# Adapter-CMRI8-RJ45.net
KiCad netlist of a schematic drawn in EAGLE
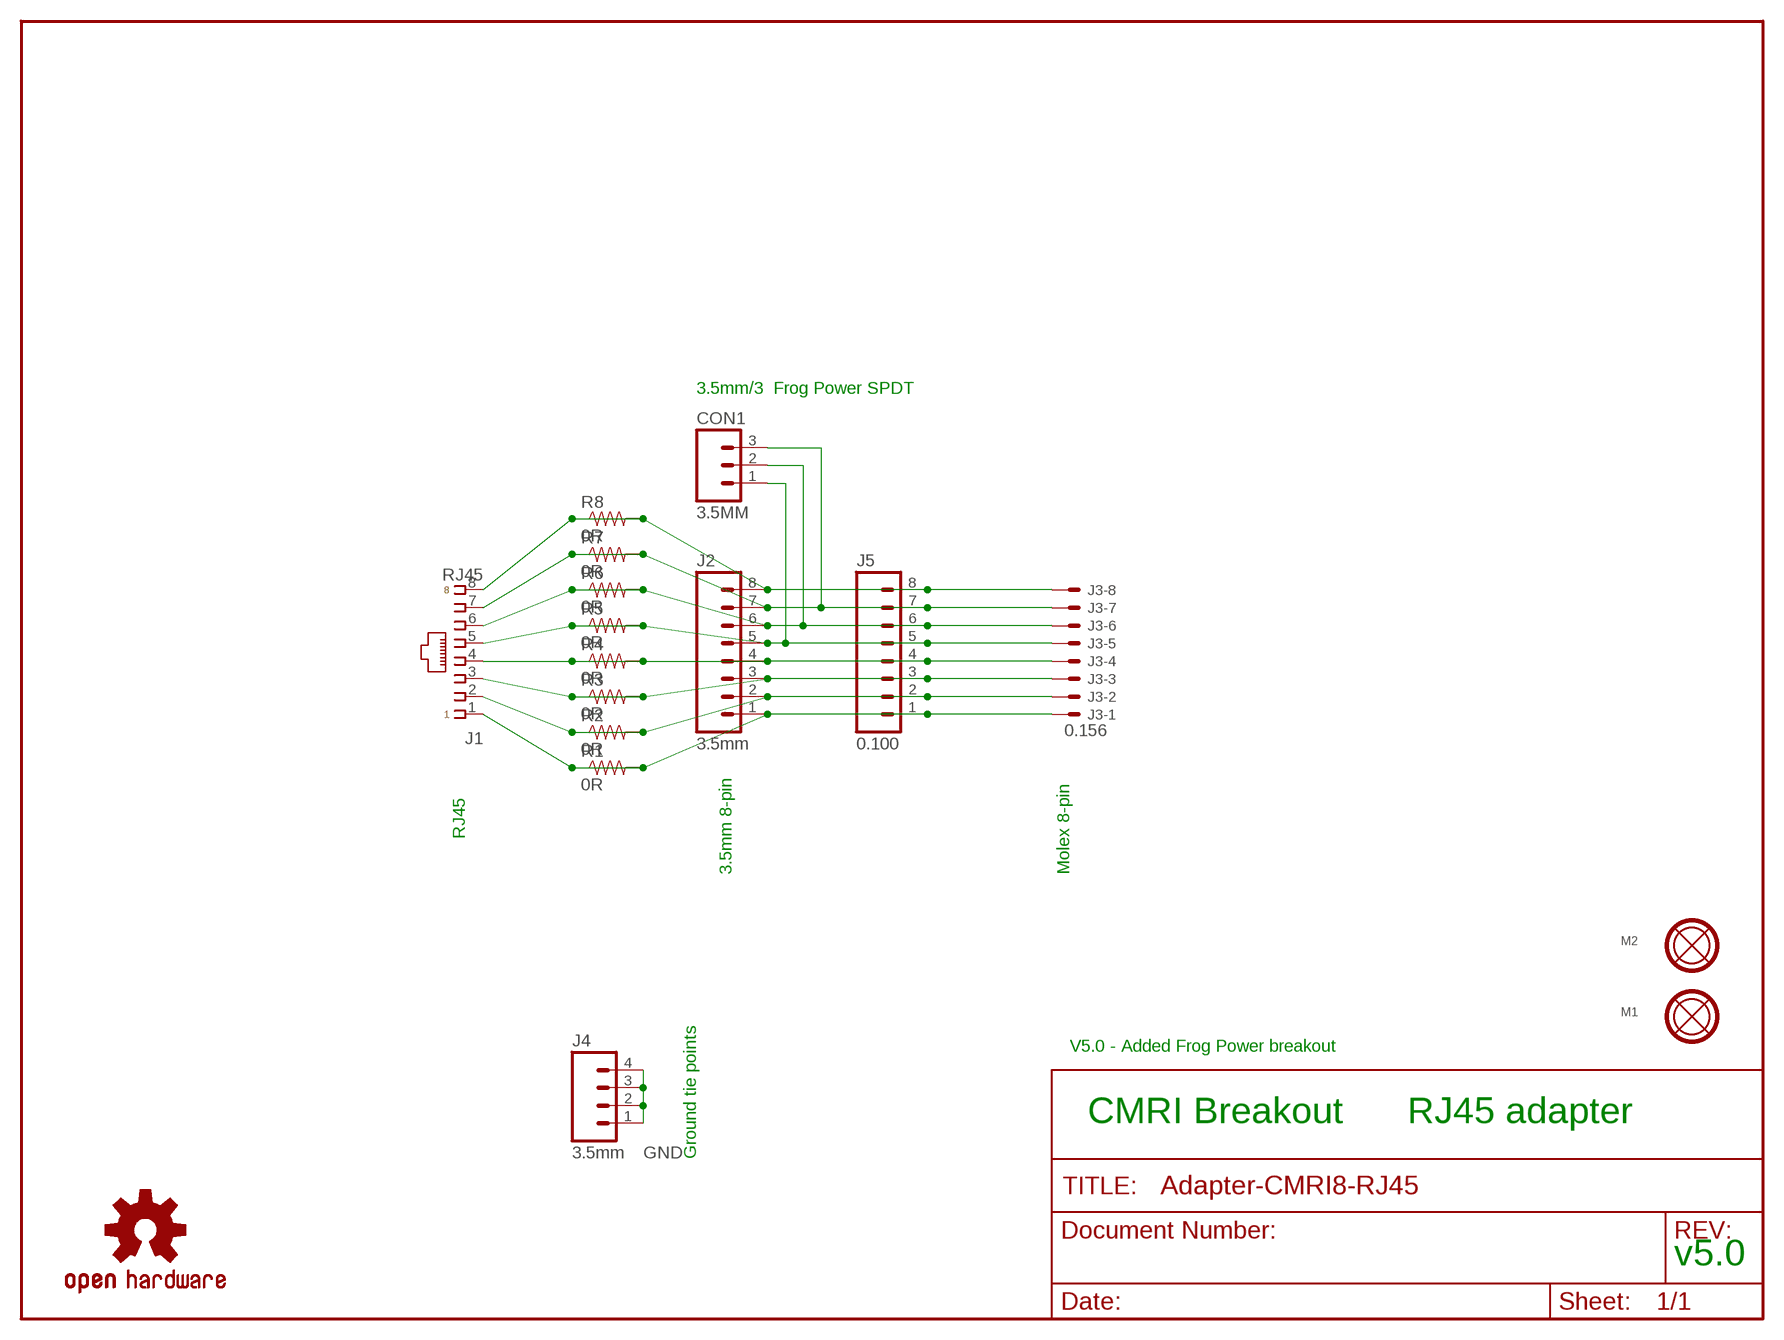
[diagram p0: schematic, sheet 1]

(export (version "E")
  (design (tool "Eeschema 10.0.6"))
  (components
    (comp (ref "CON1")
      (value "3.5MM")
      (footprint "eagle-import:SCREWTERMINAL-3.5MM-3_LOCK.007S")
      (libsource (lib "eagle-import") (part "CONNECTOR-M033.5MM-LOCK"))
    )
    (comp (ref "J1")
      (value "RJ45")
      (footprint "eagle-import:RJ45-NO-SHIELD")
      (libsource (lib "eagle-import") (part "CONNECTOR-RJ45-FRONT"))
    )
    (comp (ref "J2")
      (value "3.5mm")
      (footprint "eagle-import:SCREWTERMINAL-3.5MM-8")
      (libsource (lib "eagle-import") (part "CONNECTOR-M083.5MM-8"))
    )
    (comp (ref "J3")
      (value "0.156")
      (footprint "eagle-import:KK-156-8-F")
      (libsource (lib "eagle-import") (part "KK-156-8F"))
    )
    (comp (ref "J4")
      (value "3.5mm")
      (footprint "eagle-import:SCREWTERMINAL-3.5MM-4_LOCK")
      (libsource (lib "eagle-import") (part "CONNECTOR-M04SCREW_LOCK"))
    )
    (comp (ref "J5")
      (value "0.100")
      (footprint "eagle-import:1X08_LOCK")
      (libsource (lib "eagle-import") (part "CONNECTOR-M08LOCK"))
    )
    (comp (ref "M1")
      (value "MOUNTINGHOLE")
      (footprint "eagle-import:MOUNTINGHOLE")
      (libsource (lib "eagle-import") (part "MOUNTINGHOLE"))
    )
    (comp (ref "M2")
      (value "MOUNTINGHOLE")
      (footprint "eagle-import:MOUNTINGHOLE")
      (libsource (lib "eagle-import") (part "MOUNTINGHOLE"))
    )
    (comp (ref "R1")
      (value "0R")
      (footprint "eagle-import:AXIAL-0.4-RES")
      (libsource (lib "eagle-import") (part "RPTH04"))
    )
    (comp (ref "R2")
      (value "0R")
      (footprint "eagle-import:AXIAL-0.4-RES")
      (libsource (lib "eagle-import") (part "RPTH04"))
    )
    (comp (ref "R3")
      (value "0R")
      (footprint "eagle-import:AXIAL-0.4-RES")
      (libsource (lib "eagle-import") (part "RPTH04"))
    )
    (comp (ref "R4")
      (value "0R")
      (footprint "eagle-import:AXIAL-0.4-RES")
      (libsource (lib "eagle-import") (part "RPTH04"))
    )
    (comp (ref "R5")
      (value "0R")
      (footprint "eagle-import:AXIAL-0.4-RES")
      (libsource (lib "eagle-import") (part "RPTH04"))
    )
    (comp (ref "R6")
      (value "0R")
      (footprint "eagle-import:AXIAL-0.4-RES")
      (libsource (lib "eagle-import") (part "RPTH04"))
    )
    (comp (ref "R7")
      (value "0R")
      (footprint "eagle-import:AXIAL-0.4-RES")
      (libsource (lib "eagle-import") (part "RPTH04"))
    )
    (comp (ref "R8")
      (value "0R")
      (footprint "eagle-import:AXIAL-0.4-RES")
      (libsource (lib "eagle-import") (part "RPTH04"))
    )
    (comp (ref "U$1")
      (value "OSHW")
      (footprint "eagle-import:OSHW-LOGO-L")
      (libsource (lib "eagle-import") (part "DOC-OSHW-LOGO-L"))
    )
  )
  (nets
    (net (code "1") (name "/GND") (class "Default")
      (node (ref "J4") (pin "1") (pinfunction "1_1") (pintype "passive"))
      (node (ref "J4") (pin "2") (pinfunction "2_2") (pintype "passive"))
      (node (ref "J4") (pin "3") (pinfunction "3_3") (pintype "passive"))
      (node (ref "J4") (pin "4") (pinfunction "4_4") (pintype "passive"))
    )
    (net (code "2") (name "Net-(J3A-S)") (class "Default")
      (node (ref "J1") (pin "1") (pinfunction "1_1") (pintype "passive"))
      (node (ref "J2") (pin "1") (pinfunction "1_1") (pintype "passive"))
      (node (ref "J3") (pin "1") (pinfunction "S_1") (pintype "passive"))
      (node (ref "J5") (pin "1") (pinfunction "1_1") (pintype "passive"))
      (node (ref "R1") (pin "P$1") (pinfunction "1_P$1") (pintype "passive"))
      (node (ref "R1") (pin "P$2") (pinfunction "2_P$2") (pintype "passive"))
    )
    (net (code "3") (name "Net-(J3B-S)") (class "Default")
      (node (ref "J1") (pin "2") (pinfunction "2_2") (pintype "passive"))
      (node (ref "J2") (pin "2") (pinfunction "2_2") (pintype "passive"))
      (node (ref "J3") (pin "2") (pinfunction "S_2") (pintype "passive"))
      (node (ref "J5") (pin "2") (pinfunction "2_2") (pintype "passive"))
      (node (ref "R2") (pin "P$1") (pinfunction "1_P$1") (pintype "passive"))
      (node (ref "R2") (pin "P$2") (pinfunction "2_P$2") (pintype "passive"))
    )
    (net (code "4") (name "Net-(J3C-S)") (class "Default")
      (node (ref "J1") (pin "3") (pinfunction "3_3") (pintype "passive"))
      (node (ref "J2") (pin "3") (pinfunction "3_3") (pintype "passive"))
      (node (ref "J3") (pin "3") (pinfunction "S_3") (pintype "passive"))
      (node (ref "J5") (pin "3") (pinfunction "3_3") (pintype "passive"))
      (node (ref "R3") (pin "P$1") (pinfunction "1_P$1") (pintype "passive"))
      (node (ref "R3") (pin "P$2") (pinfunction "2_P$2") (pintype "passive"))
    )
    (net (code "5") (name "Net-(J3D-S)") (class "Default")
      (node (ref "J1") (pin "4") (pinfunction "4_4") (pintype "passive"))
      (node (ref "J2") (pin "4") (pinfunction "4_4") (pintype "passive"))
      (node (ref "J3") (pin "4") (pinfunction "S_4") (pintype "passive"))
      (node (ref "J5") (pin "4") (pinfunction "4_4") (pintype "passive"))
      (node (ref "R4") (pin "P$1") (pinfunction "1_P$1") (pintype "passive"))
      (node (ref "R4") (pin "P$2") (pinfunction "2_P$2") (pintype "passive"))
    )
    (net (code "6") (name "Net-(J3E-S)") (class "Default")
      (node (ref "CON1") (pin "1") (pinfunction "1_1") (pintype "passive"))
      (node (ref "J1") (pin "5") (pinfunction "5_5") (pintype "passive"))
      (node (ref "J2") (pin "5") (pinfunction "5_5") (pintype "passive"))
      (node (ref "J3") (pin "5") (pinfunction "S_5") (pintype "passive"))
      (node (ref "J5") (pin "5") (pinfunction "5_5") (pintype "passive"))
      (node (ref "R5") (pin "P$1") (pinfunction "1_P$1") (pintype "passive"))
      (node (ref "R5") (pin "P$2") (pinfunction "2_P$2") (pintype "passive"))
    )
    (net (code "7") (name "Net-(J3F-S)") (class "Default")
      (node (ref "CON1") (pin "2") (pinfunction "2_2") (pintype "passive"))
      (node (ref "J1") (pin "6") (pinfunction "6_6") (pintype "passive"))
      (node (ref "J2") (pin "6") (pinfunction "6_6") (pintype "passive"))
      (node (ref "J3") (pin "6") (pinfunction "S_6") (pintype "passive"))
      (node (ref "J5") (pin "6") (pinfunction "6_6") (pintype "passive"))
      (node (ref "R6") (pin "P$1") (pinfunction "1_P$1") (pintype "passive"))
      (node (ref "R6") (pin "P$2") (pinfunction "2_P$2") (pintype "passive"))
    )
    (net (code "8") (name "Net-(J3G-S)") (class "Default")
      (node (ref "CON1") (pin "3") (pinfunction "3_3") (pintype "passive"))
      (node (ref "J1") (pin "7") (pinfunction "7_7") (pintype "passive"))
      (node (ref "J2") (pin "7") (pinfunction "7_7") (pintype "passive"))
      (node (ref "J3") (pin "7") (pinfunction "S_7") (pintype "passive"))
      (node (ref "J5") (pin "7") (pinfunction "7_7") (pintype "passive"))
      (node (ref "R7") (pin "P$1") (pinfunction "1_P$1") (pintype "passive"))
      (node (ref "R7") (pin "P$2") (pinfunction "2_P$2") (pintype "passive"))
    )
    (net (code "9") (name "Net-(J3H-S)") (class "Default")
      (node (ref "J1") (pin "8") (pinfunction "8_8") (pintype "passive"))
      (node (ref "J2") (pin "8") (pinfunction "8_8") (pintype "passive"))
      (node (ref "J3") (pin "8") (pinfunction "S_8") (pintype "passive"))
      (node (ref "J5") (pin "8") (pinfunction "8_8") (pintype "passive"))
      (node (ref "R8") (pin "P$1") (pinfunction "1_P$1") (pintype "passive"))
      (node (ref "R8") (pin "P$2") (pinfunction "2_P$2") (pintype "passive"))
    )
  )
)
